# 687253_017_3_1.net
KiCad netlist of a schematic drawn in Altium Designer
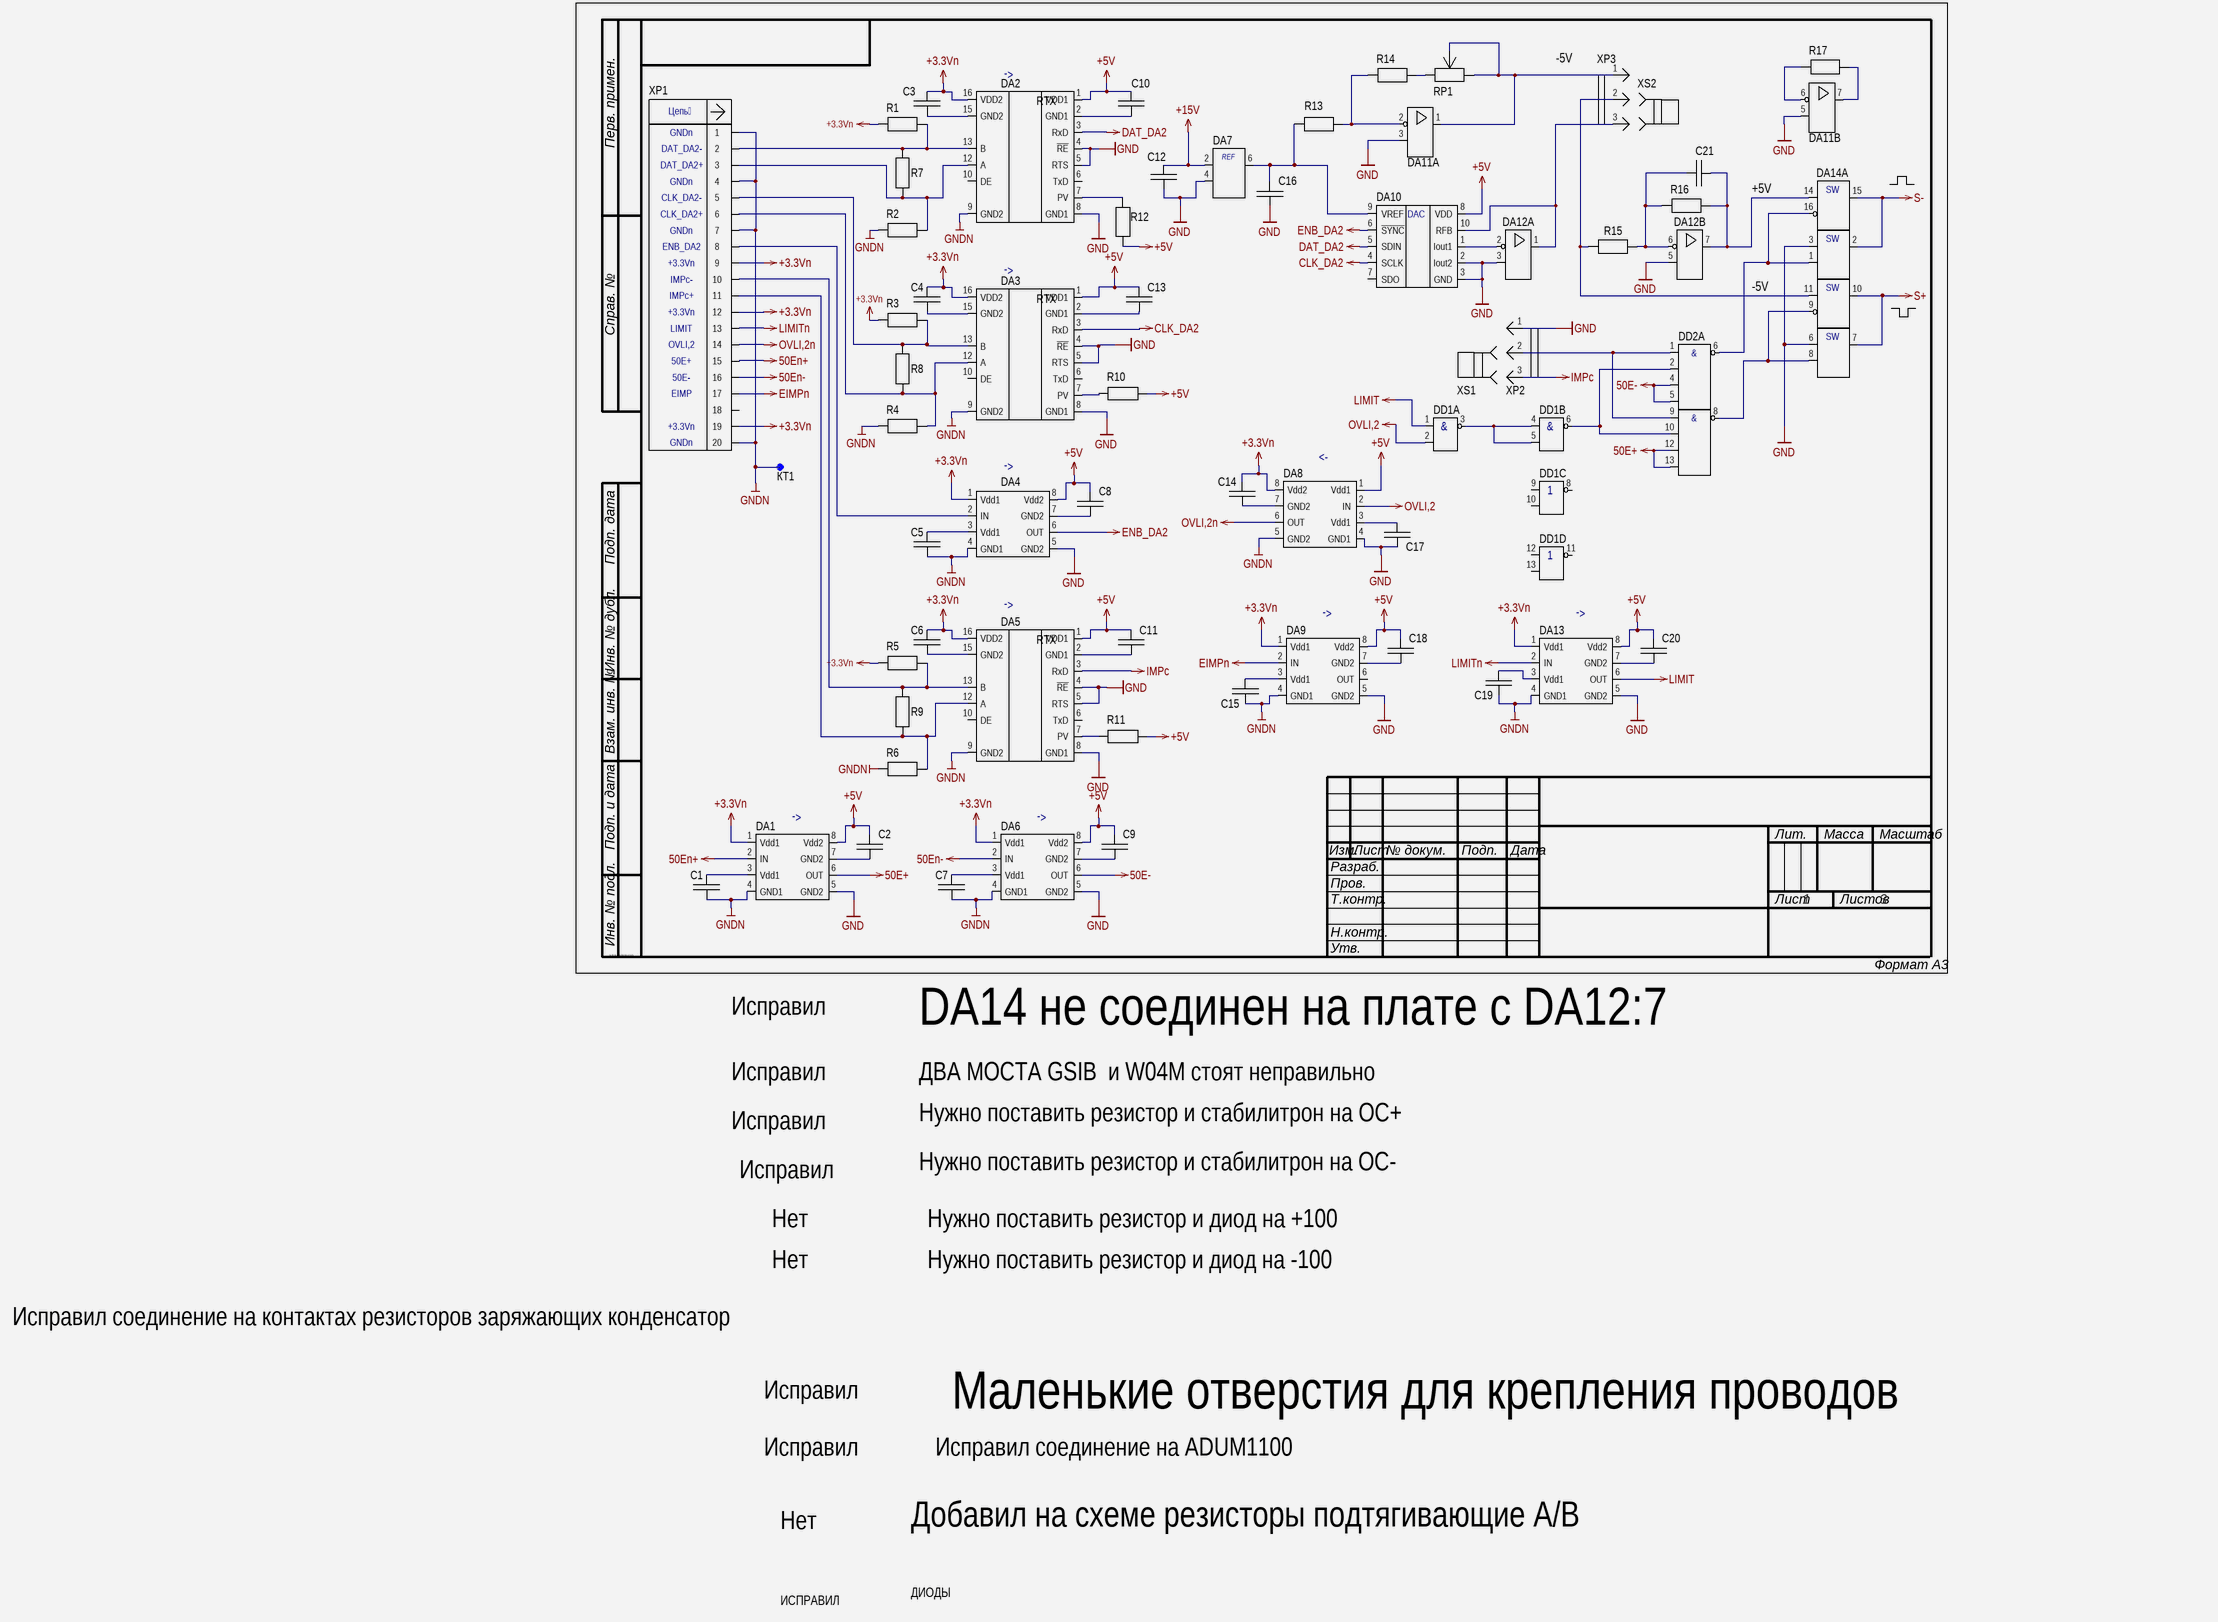
[diagram p0: УШЯИ687253.017Э3_1.SchDoc]

(export (version "E")
  (design (tool "Eeschema 10.0.6"))
  (components
    (comp (ref "C1")
      (value "0805-X7R-25 В-0,1 мкФ +-10%")
      (footprint "standard-case:CAP: 0805")
      (libsource (lib "МНИПИ_Конденсаторы") (part "0805-X7R-25 В-0,1 мкФ +-10%"))
    )
    (comp (ref "C2")
      (value "0805-X7R-25 В-0,1 мкФ +-10%")
      (footprint "standard-case:CAP: 0805")
      (libsource (lib "МНИПИ_Конденсаторы") (part "0805-X7R-25 В-0,1 мкФ +-10%"))
    )
    (comp (ref "C3")
      (value "0805-X7R-25 В-0,1 мкФ +-10%")
      (footprint "standard-case:CAP: 0805")
      (libsource (lib "МНИПИ_Конденсаторы") (part "0805-X7R-25 В-0,1 мкФ +-10%"))
    )
    (comp (ref "C4")
      (value "0805-X7R-25 В-0,1 мкФ +-10%")
      (footprint "standard-case:CAP: 0805")
      (libsource (lib "МНИПИ_Конденсаторы") (part "0805-X7R-25 В-0,1 мкФ +-10%"))
    )
    (comp (ref "C5")
      (value "0805-X7R-25 В-0,1 мкФ +-10%")
      (footprint "standard-case:CAP: 0805")
      (libsource (lib "МНИПИ_Конденсаторы") (part "0805-X7R-25 В-0,1 мкФ +-10%"))
    )
    (comp (ref "C6")
      (value "0805-X7R-25 В-0,1 мкФ +-10%")
      (footprint "standard-case:CAP: 0805")
      (libsource (lib "МНИПИ_Конденсаторы") (part "0805-X7R-25 В-0,1 мкФ +-10%"))
    )
    (comp (ref "C7")
      (value "0805-X7R-25 В-0,1 мкФ +-10%")
      (footprint "standard-case:CAP: 0805")
      (libsource (lib "МНИПИ_Конденсаторы") (part "0805-X7R-25 В-0,1 мкФ +-10%"))
    )
    (comp (ref "C8")
      (value "0805-X7R-25 В-0,1 мкФ +-10%")
      (footprint "standard-case:CAP: 0805")
      (libsource (lib "МНИПИ_Конденсаторы") (part "0805-X7R-25 В-0,1 мкФ +-10%"))
    )
    (comp (ref "C9")
      (value "0805-X7R-25 В-0,1 мкФ +-10%")
      (footprint "standard-case:CAP: 0805")
      (libsource (lib "МНИПИ_Конденсаторы") (part "0805-X7R-25 В-0,1 мкФ +-10%"))
    )
    (comp (ref "C10")
      (value "0805-X7R-25 В-0,1 мкФ +-10%")
      (footprint "standard-case:CAP: 0805")
      (libsource (lib "МНИПИ_Конденсаторы") (part "0805-X7R-25 В-0,1 мкФ +-10%"))
    )
    (comp (ref "C11")
      (value "0805-X7R-25 В-0,1 мкФ +-10%")
      (footprint "standard-case:CAP: 0805")
      (libsource (lib "МНИПИ_Конденсаторы") (part "0805-X7R-25 В-0,1 мкФ +-10%"))
    )
    (comp (ref "C12")
      (value "0805-X7R-25 В-0,1 мкФ +-10%")
      (footprint "standard-case:CAP: 0805")
      (libsource (lib "МНИПИ_Конденсаторы") (part "0805-X7R-25 В-0,1 мкФ +-10%"))
    )
    (comp (ref "C13")
      (value "0805-X7R-25 В-0,1 мкФ +-10%")
      (footprint "standard-case:CAP: 0805")
      (libsource (lib "МНИПИ_Конденсаторы") (part "0805-X7R-25 В-0,1 мкФ +-10%"))
    )
    (comp (ref "C14")
      (value "0805-X7R-25 В-0,1 мкФ +-10%")
      (footprint "standard-case:CAP: 0805")
      (libsource (lib "МНИПИ_Конденсаторы") (part "0805-X7R-25 В-0,1 мкФ +-10%"))
    )
    (comp (ref "C15")
      (value "0805-X7R-25 В-0,1 мкФ +-10%")
      (footprint "standard-case:CAP: 0805")
      (libsource (lib "МНИПИ_Конденсаторы") (part "0805-X7R-25 В-0,1 мкФ +-10%"))
    )
    (comp (ref "C16")
      (value "0805-X7R-25 В-0,1 мкФ +-10%")
      (footprint "standard-case:CAP: 0805")
      (libsource (lib "МНИПИ_Конденсаторы") (part "0805-X7R-25 В-0,1 мкФ +-10%"))
    )
    (comp (ref "C17")
      (value "0805-X7R-25 В-0,1 мкФ +-10%")
      (footprint "standard-case:CAP: 0805")
      (libsource (lib "МНИПИ_Конденсаторы") (part "0805-X7R-25 В-0,1 мкФ +-10%"))
    )
    (comp (ref "C18")
      (value "0805-X7R-25 В-0,1 мкФ +-10%")
      (footprint "standard-case:CAP: 0805")
      (libsource (lib "МНИПИ_Конденсаторы") (part "0805-X7R-25 В-0,1 мкФ +-10%"))
    )
    (comp (ref "C19")
      (value "0805-X7R-25 В-0,1 мкФ +-10%")
      (footprint "standard-case:CAP: 0805")
      (libsource (lib "МНИПИ_Конденсаторы") (part "0805-X7R-25 В-0,1 мкФ +-10%"))
    )
    (comp (ref "C20")
      (value "0805-X7R-25 В-0,1 мкФ +-10%")
      (footprint "standard-case:CAP: 0805")
      (libsource (lib "МНИПИ_Конденсаторы") (part "0805-X7R-25 В-0,1 мкФ +-10%"))
    )
    (comp (ref "C21")
      (value "1206-C0G-50 В-22 пФ +-5%")
      (footprint "standard-case:CAP: 1206")
      (libsource (lib "МНИПИ_Конденсаторы") (part "1206-C0G-50 В-22 пФ +-5%"))
    )
    (comp (ref "DA1")
      (value "ADuM1100AR")
      (footprint "standard-case:8-SOIC")
      (description "iCoupler Digital Isolator")
      (libsource (lib "МНИПИ_Микросхемы") (part "ADuM1100AR"))
    )
    (comp (ref "DA2")
      (value "ADM2486BRWZ")
      (footprint "16-SOIC-W")
      (description "Isolated RS-485 Transceiver,  20 Mbps data rate, SOIC-16-W")
      (libsource (lib "МНИПИ_Микросхемы") (part "ADM2486BRWZ"))
    )
    (comp (ref "DA3")
      (value "ADM2486BRWZ")
      (footprint "16-SOIC-W")
      (description "Isolated RS-485 Transceiver,  20 Mbps data rate, SOIC-16-W")
      (libsource (lib "МНИПИ_Микросхемы") (part "ADM2486BRWZ"))
    )
    (comp (ref "DA4")
      (value "ADuM1100AR")
      (footprint "standard-case:8-SOIC")
      (description "iCoupler Digital Isolator")
      (libsource (lib "МНИПИ_Микросхемы") (part "ADuM1100AR"))
    )
    (comp (ref "DA5")
      (value "ADM2486BRWZ")
      (footprint "16-SOIC-W")
      (description "Isolated RS-485 Transceiver,  20 Mbps data rate, SOIC-16-W")
      (libsource (lib "МНИПИ_Микросхемы") (part "ADM2486BRWZ"))
    )
    (comp (ref "DA6")
      (value "ADuM1100AR")
      (footprint "standard-case:8-SOIC")
      (description "iCoupler Digital Isolator")
      (libsource (lib "МНИПИ_Микросхемы") (part "ADuM1100AR"))
    )
    (comp (ref "DA7")
      (value "ADR435BRZ")
      (footprint "standard-case:8-SOIC")
      (libsource (lib "МНИПИ_Микросхемы") (part "ADR435BRZ"))
    )
    (comp (ref "DA8")
      (value "ADuM1100AR")
      (footprint "standard-case:8-SOIC")
      (description "iCoupler Digital Isolator")
      (libsource (lib "") (part "ADuM1100AR_1"))
    )
    (comp (ref "DA9")
      (value "ADuM1100AR")
      (footprint "standard-case:8-SOIC")
      (description "iCoupler Digital Isolator")
      (libsource (lib "МНИПИ_Микросхемы") (part "ADuM1100AR"))
    )
    (comp (ref "DA10")
      (value "AD5443YRM")
      (footprint "10-MSOP")
      (description "12-Bit High Bandwidth\r\nMultiplying DACs with Serial Interface\r10-MSOP")
      (libsource (lib "МНИПИ_Микросхемы") (part "AD5443YRM"))
    )
    (comp (ref "DA11")
      (value "ADA4084-2ARZ")
      (footprint "standard-case:8-SOIC")
      (description "30 V, Low Noise, Rail-to-Rail Input/Output,\r\nLow Power Operational Amplifiers")
      (libsource (lib "МНИПИ_Микросхемы") (part "ADA4084-2ARZ"))
    )
    (comp (ref "DA12")
      (value "ADA4084-2ARZ")
      (footprint "standard-case:8-SOIC")
      (description "30 V, Low Noise, Rail-to-Rail Input/Output,\r\nLow Power Operational Amplifiers")
      (libsource (lib "МНИПИ_Микросхемы") (part "ADA4084-2ARZ"))
    )
    (comp (ref "DA13")
      (value "ADuM1100AR")
      (footprint "standard-case:8-SOIC")
      (description "iCoupler Digital Isolator")
      (libsource (lib "МНИПИ_Микросхемы") (part "ADuM1100AR"))
    )
    (comp (ref "DA14")
      (value "ADG433BR")
      (footprint "standard-case:16-SOIC")
      (description "LC2MOS Precision Quad SPST Switches")
      (libsource (lib "МНИПИ_Микросхемы") (part "ADG433BR_1"))
    )
    (comp (ref "DD1")
      (value "IN74HC00AD")
      (footprint "standard-case:14-soic")
      (description "Quad 2-Input NAND Gate High-Performance Silicon-Gate CMOS.")
      (libsource (lib "МНИПИ_Микросхемы") (part "IN74HC00AD"))
    )
    (comp (ref "DD2")
      (value "IN74HC20D")
      (footprint "standard-case:14-SOIC")
      (description "Dual 4-input  NAND Gate CMOS")
      (libsource (lib "МНИПИ_Микросхемы") (part "IN74HC20D_1"))
    )
    (comp (ref "R1")
      (value "1206-1 кОм+-5%")
      (footprint "МНИПИ_Резисторы:1206")
      (libsource (lib "МНИПИ_Резисторы") (part "1206-1 кОм+-5%"))
    )
    (comp (ref "R2")
      (value "1206-1 кОм+-5%")
      (footprint "МНИПИ_Резисторы:1206")
      (libsource (lib "МНИПИ_Резисторы") (part "1206-1 кОм+-5%"))
    )
    (comp (ref "R3")
      (value "1206-1 кОм+-5%")
      (footprint "МНИПИ_Резисторы:1206")
      (libsource (lib "МНИПИ_Резисторы") (part "1206-1 кОм+-5%"))
    )
    (comp (ref "R4")
      (value "1206-1 кОм+-5%")
      (footprint "МНИПИ_Резисторы:1206")
      (libsource (lib "МНИПИ_Резисторы") (part "1206-1 кОм+-5%"))
    )
    (comp (ref "R5")
      (value "1206-1 кОм+-5%")
      (footprint "МНИПИ_Резисторы:1206")
      (libsource (lib "МНИПИ_Резисторы") (part "1206-1 кОм+-5%"))
    )
    (comp (ref "R6")
      (value "1206-1 кОм+-5%")
      (footprint "МНИПИ_Резисторы:1206")
      (libsource (lib "МНИПИ_Резисторы") (part "1206-1 кОм+-5%"))
    )
    (comp (ref "R7")
      (value "1206-100 Ом+-5%")
      (footprint "МНИПИ_Резисторы:1206")
      (libsource (lib "МНИПИ_Резисторы") (part "1206-100 Ом+-5%"))
    )
    (comp (ref "R8")
      (value "1206-100 Ом+-5%")
      (footprint "МНИПИ_Резисторы:1206")
      (libsource (lib "МНИПИ_Резисторы") (part "1206-100 Ом+-5%"))
    )
    (comp (ref "R9")
      (value "1206-100 Ом+-5%")
      (footprint "МНИПИ_Резисторы:1206")
      (libsource (lib "МНИПИ_Резисторы") (part "1206-100 Ом+-5%"))
    )
    (comp (ref "R10")
      (value "1206-12 кОм+-5%")
      (footprint "МНИПИ_Резисторы:1206")
      (libsource (lib "МНИПИ_Резисторы") (part "1206-12 кОм+-5%"))
    )
    (comp (ref "R11")
      (value "1206-12 кОм+-5%")
      (footprint "МНИПИ_Резисторы:1206")
      (libsource (lib "МНИПИ_Резисторы") (part "1206-12 кОм+-5%"))
    )
    (comp (ref "R12")
      (value "1206-12 кОм+-5%")
      (footprint "МНИПИ_Резисторы:1206")
      (libsource (lib "МНИПИ_Резисторы") (part "1206-12 кОм+-5%"))
    )
    (comp (ref "R13")
      (value "1206-10 кОм+-0,5%")
      (footprint "МНИПИ_Резисторы:1206")
      (libsource (lib "МНИПИ_Резисторы") (part "1206-10 кОм+-0,5%"))
    )
    (comp (ref "R14")
      (value "1206-100 Ом+-0,5%")
      (footprint "МНИПИ_Резисторы:1206")
      (libsource (lib "МНИПИ_Резисторы") (part "1206-100 Ом+-0,5%"))
    )
    (comp (ref "R15")
      (value "1206-10 кОм+-0,5%")
      (footprint "МНИПИ_Резисторы:1206")
      (libsource (lib "МНИПИ_Резисторы") (part "1206-10 кОм+-0,5%"))
    )
    (comp (ref "R16")
      (value "1206-10 кОм+-0,5%")
      (footprint "МНИПИ_Резисторы:1206")
      (libsource (lib "МНИПИ_Резисторы") (part "1206-10 кОм+-0,5%"))
    )
    (comp (ref "R17")
      (value "1206-12 кОм+-1%")
      (footprint "МНИПИ_Резисторы:1206")
      (libsource (lib "МНИПИ_Резисторы") (part "1206-12 кОм+-1%"))
    )
    (comp (ref "RP1")
      (value "3362P-1-103LF")
      (footprint "BOUR-3362P")
      (description "3362 -1/4 ˝ Square Trimpot® Trimming Potentiometer")
      (libsource (lib "МНИПИ_Резисторы") (part "3362P-1-103LF"))
    )
    (comp (ref "XP1")
      (value "BH2-20")
      (footprint "DS1014-20S")
      (description "pitch 2mm, 20 pin 2x10")
      (libsource (lib "МНИПИ_Разъемы") (part "BH2-20"))
    )
    (comp (ref "XP2")
      (value "DS1021-1x3")
      (footprint "DS1021-1x3S")
      (description "PLS-3, 2.54 pitch")
      (libsource (lib "МНИПИ_Разъемы") (part "DS1021-1x3_1"))
    )
    (comp (ref "XP3")
      (value "DS1021-1x3")
      (footprint "DS1021-1x3S")
      (description "PLS-3, 2.54 pitch")
      (libsource (lib "МНИПИ_Разъемы") (part "DS1021-1x3_1"))
    )
    (comp (ref "XS1") (value "Jumper, 2.54mm") (libsource (lib "МНИПИ_Разъемы") (part "Jumper, 2.54mm")))
    (comp (ref "XS2") (value "Jumper, 2.54mm") (libsource (lib "МНИПИ_Разъемы") (part "Jumper, 2.54mm")))
    (comp (ref "КТ1")
      (value "Лепесток")
      (footprint "LEPESTOK7750224")
      (libsource (lib "МНИПИ_Разъемы") (part "Lepestok"))
    )
  )
  (nets
    (net (code "1") (name "+3.3Vn") (class "Default")
      (node (ref "C14") (pin "1") (pinfunction "1_1") (pintype "passive"))
      (node (ref "C3") (pin "2") (pinfunction "2_2") (pintype "passive"))
      (node (ref "C4") (pin "2") (pinfunction "2_2") (pintype "passive"))
      (node (ref "C6") (pin "2") (pinfunction "2_2") (pintype "passive"))
      (node (ref "DA1") (pin "1") (pinfunction "Vdd1_1") (pintype "passive"))
      (node (ref "DA13") (pin "1") (pinfunction "Vdd1_1") (pintype "passive"))
      (node (ref "DA2") (pin "16") (pinfunction "VDD2_16") (pintype "passive"))
      (node (ref "DA3") (pin "16") (pinfunction "VDD2_16") (pintype "passive"))
      (node (ref "DA4") (pin "1") (pinfunction "Vdd1_1") (pintype "passive"))
      (node (ref "DA5") (pin "16") (pinfunction "VDD2_16") (pintype "passive"))
      (node (ref "DA6") (pin "1") (pinfunction "Vdd1_1") (pintype "passive"))
      (node (ref "DA8") (pin "8") (pinfunction "Vdd2_8") (pintype "passive"))
      (node (ref "DA9") (pin "1") (pinfunction "Vdd1_1") (pintype "passive"))
      (node (ref "R1") (pin "2") (pinfunction "2_2") (pintype "passive"))
      (node (ref "R3") (pin "2") (pinfunction "2_2") (pintype "passive"))
      (node (ref "R5") (pin "2") (pinfunction "2_2") (pintype "passive"))
      (node (ref "XP1") (pin "12") (pinfunction "12_12") (pintype "passive"))
      (node (ref "XP1") (pin "19") (pinfunction "19_19") (pintype "passive"))
      (node (ref "XP1") (pin "9") (pinfunction "9_9") (pintype "passive"))
    )
    (net (code "2") (name "+5V") (class "Default")
      (node (ref "C10") (pin "2") (pinfunction "2_2") (pintype "passive"))
      (node (ref "C11") (pin "2") (pinfunction "2_2") (pintype "passive"))
      (node (ref "C13") (pin "2") (pinfunction "2_2") (pintype "passive"))
      (node (ref "C18") (pin "1") (pinfunction "1_1") (pintype "passive"))
      (node (ref "C2") (pin "1") (pinfunction "1_1") (pintype "passive"))
      (node (ref "C20") (pin "1") (pinfunction "1_1") (pintype "passive"))
      (node (ref "C8") (pin "1") (pinfunction "1_1") (pintype "passive"))
      (node (ref "C9") (pin "1") (pinfunction "1_1") (pintype "passive"))
      (node (ref "DA1") (pin "8") (pinfunction "Vdd2_8") (pintype "passive"))
      (node (ref "DA10") (pin "8") (pinfunction "VDD_8") (pintype "passive"))
      (node (ref "DA13") (pin "8") (pinfunction "Vdd2_8") (pintype "passive"))
      (node (ref "DA2") (pin "1") (pinfunction "VDD1_1") (pintype "passive"))
      (node (ref "DA3") (pin "1") (pinfunction "VDD1_1") (pintype "passive"))
      (node (ref "DA4") (pin "8") (pinfunction "Vdd2_8") (pintype "passive"))
      (node (ref "DA5") (pin "1") (pinfunction "VDD1_1") (pintype "passive"))
      (node (ref "DA6") (pin "8") (pinfunction "Vdd2_8") (pintype "passive"))
      (node (ref "DA8") (pin "1") (pinfunction "Vdd1_1") (pintype "passive"))
      (node (ref "DA9") (pin "8") (pinfunction "Vdd2_8") (pintype "passive"))
      (node (ref "R10") (pin "1") (pinfunction "1_1") (pintype "passive"))
      (node (ref "R11") (pin "1") (pinfunction "1_1") (pintype "passive"))
      (node (ref "R12") (pin "1") (pinfunction "1_1") (pintype "passive"))
    )
    (net (code "3") (name "+15V") (class "Default")
      (node (ref "C12") (pin "1") (pinfunction "1_1") (pintype "passive"))
      (node (ref "DA7") (pin "2") (pinfunction "VIN_2") (pintype "passive"))
    )
    (net (code "4") (name "50E+") (class "Default")
      (node (ref "DA1") (pin "6") (pinfunction "OUT_6") (pintype "passive"))
      (node (ref "DD2") (pin "12") (pinfunction "C2_12") (pintype "passive"))
      (node (ref "DD2") (pin "13") (pinfunction "D2_13") (pintype "passive"))
    )
    (net (code "5") (name "50E-") (class "Default")
      (node (ref "DA6") (pin "6") (pinfunction "OUT_6") (pintype "passive"))
      (node (ref "DD2") (pin "4") (pinfunction "C1_4") (pintype "passive"))
      (node (ref "DD2") (pin "5") (pinfunction "D1_5") (pintype "passive"))
    )
    (net (code "6") (name "50En+") (class "Default")
      (node (ref "DA1") (pin "2") (pinfunction "IN_2") (pintype "passive"))
      (node (ref "XP1") (pin "15") (pinfunction "15_15") (pintype "passive"))
    )
    (net (code "7") (name "50En-") (class "Default")
      (node (ref "DA6") (pin "2") (pinfunction "IN_2") (pintype "passive"))
      (node (ref "XP1") (pin "16") (pinfunction "16_16") (pintype "passive"))
    )
    (net (code "8") (name "CLK_DA2") (class "Default")
      (node (ref "DA10") (pin "4") (pinfunction "SCLK_4") (pintype "passive"))
      (node (ref "DA3") (pin "3") (pinfunction "RxD_3") (pintype "passive"))
    )
    (net (code "9") (name "DAT_DA2") (class "Default")
      (node (ref "DA10") (pin "5") (pinfunction "SDIN_5") (pintype "passive"))
      (node (ref "DA2") (pin "3") (pinfunction "RxD_3") (pintype "passive"))
    )
    (net (code "10") (name "EIMPn") (class "Default")
      (node (ref "DA9") (pin "2") (pinfunction "IN_2") (pintype "passive"))
      (node (ref "XP1") (pin "17") (pinfunction "17_17") (pintype "passive"))
    )
    (net (code "11") (name "ENB_DA2") (class "Default")
      (node (ref "DA10") (pin "6") (pinfunction "SYNC_6") (pintype "passive"))
      (node (ref "DA4") (pin "6") (pinfunction "OUT_6") (pintype "passive"))
    )
    (net (code "12") (name "GND") (class "Default")
      (node (ref "C12") (pin "2") (pinfunction "2_2") (pintype "passive"))
      (node (ref "C16") (pin "1") (pinfunction "1_1") (pintype "passive"))
      (node (ref "C17") (pin "1") (pinfunction "1_1") (pintype "passive"))
      (node (ref "DA1") (pin "5") (pinfunction "GND2_5") (pintype "passive"))
      (node (ref "DA10") (pin "2") (pinfunction "Iout2_2") (pintype "passive"))
      (node (ref "DA10") (pin "3") (pinfunction "GND_3") (pintype "passive"))
      (node (ref "DA11") (pin "3") (pinfunction "+IN_A_3") (pintype "passive"))
      (node (ref "DA11") (pin "5") (pinfunction "+IN_B_5") (pintype "passive"))
      (node (ref "DA12") (pin "3") (pinfunction "+IN_A_3") (pintype "passive"))
      (node (ref "DA12") (pin "5") (pinfunction "+IN_B_5") (pintype "passive"))
      (node (ref "DA13") (pin "5") (pinfunction "GND2_5") (pintype "passive"))
      (node (ref "DA14") (pin "3") (pinfunction "S1_3") (pintype "passive"))
      (node (ref "DA14") (pin "6") (pinfunction "S4_6") (pintype "passive"))
      (node (ref "DA2") (pin "4") (pinfunction "RE_4") (pintype "passive"))
      (node (ref "DA2") (pin "5") (pinfunction "RTS_5") (pintype "passive"))
      (node (ref "DA2") (pin "8") (pinfunction "GND1_8") (pintype "passive"))
      (node (ref "DA3") (pin "4") (pinfunction "RE_4") (pintype "passive"))
      (node (ref "DA3") (pin "5") (pinfunction "RTS_5") (pintype "passive"))
      (node (ref "DA3") (pin "8") (pinfunction "GND1_8") (pintype "passive"))
      (node (ref "DA4") (pin "5") (pinfunction "GND2_5") (pintype "passive"))
      (node (ref "DA5") (pin "4") (pinfunction "RE_4") (pintype "passive"))
      (node (ref "DA5") (pin "5") (pinfunction "RTS_5") (pintype "passive"))
      (node (ref "DA5") (pin "8") (pinfunction "GND1_8") (pintype "passive"))
      (node (ref "DA6") (pin "5") (pinfunction "GND2_5") (pintype "passive"))
      (node (ref "DA7") (pin "4") (pinfunction "GND_4") (pintype "passive"))
      (node (ref "DA8") (pin "4") (pinfunction "GND1_4") (pintype "passive"))
      (node (ref "DA9") (pin "5") (pinfunction "GND2_5") (pintype "passive"))
      (node (ref "XP2") (pin "1") (pinfunction "1_1") (pintype "passive"))
    )
    (net (code "13") (name "GNDN") (class "Default")
      (node (ref "C1") (pin "1") (pinfunction "1_1") (pintype "passive"))
      (node (ref "C15") (pin "1") (pinfunction "1_1") (pintype "passive"))
      (node (ref "C19") (pin "1") (pinfunction "1_1") (pintype "passive"))
      (node (ref "C5") (pin "1") (pinfunction "1_1") (pintype "passive"))
      (node (ref "C7") (pin "1") (pinfunction "1_1") (pintype "passive"))
      (node (ref "DA1") (pin "4") (pinfunction "GND1_4") (pintype "passive"))
      (node (ref "DA13") (pin "4") (pinfunction "GND1_4") (pintype "passive"))
      (node (ref "DA2") (pin "9") (pinfunction "GND2_9") (pintype "passive"))
      (node (ref "DA3") (pin "9") (pinfunction "GND2_9") (pintype "passive"))
      (node (ref "DA4") (pin "4") (pinfunction "GND1_4") (pintype "passive"))
      (node (ref "DA5") (pin "9") (pinfunction "GND2_9") (pintype "passive"))
      (node (ref "DA6") (pin "4") (pinfunction "GND1_4") (pintype "passive"))
      (node (ref "DA8") (pin "5") (pinfunction "GND2_5") (pintype "passive"))
      (node (ref "DA9") (pin "4") (pinfunction "GND1_4") (pintype "passive"))
      (node (ref "R2") (pin "1") (pinfunction "1_1") (pintype "passive"))
      (node (ref "R4") (pin "1") (pinfunction "1_1") (pintype "passive"))
      (node (ref "R6") (pin "1") (pinfunction "1_1") (pintype "passive"))
      (node (ref "XP1") (pin "1") (pinfunction "1_1") (pintype "passive"))
      (node (ref "XP1") (pin "20") (pinfunction "20_20") (pintype "passive"))
      (node (ref "XP1") (pin "4") (pinfunction "4_4") (pintype "passive"))
      (node (ref "XP1") (pin "7") (pinfunction "7_7") (pintype "passive"))
      (node (ref "КТ1") (pin "1") (pinfunction "1_1") (pintype "passive"))
    )
    (net (code "14") (name "IMPc") (class "Default")
      (node (ref "DA5") (pin "3") (pinfunction "RxD_3") (pintype "passive"))
      (node (ref "XP2") (pin "3") (pinfunction "3_3") (pintype "passive"))
    )
    (net (code "15") (name "LIMIT") (class "Default")
      (node (ref "DA13") (pin "6") (pinfunction "OUT_6") (pintype "passive"))
      (node (ref "DD1") (pin "1") (pinfunction "A1_1") (pintype "passive"))
    )
    (net (code "16") (name "LIMITn") (class "Default")
      (node (ref "DA13") (pin "2") (pinfunction "IN_2") (pintype "passive"))
      (node (ref "XP1") (pin "13") (pinfunction "13_13") (pintype "passive"))
    )
    (net (code "17") (name "Net-(C1-Pad2)") (class "Default")
      (node (ref "C1") (pin "2") (pinfunction "2_2") (pintype "passive"))
      (node (ref "DA1") (pin "3") (pinfunction "Vdd1_3") (pintype "passive"))
    )
    (net (code "18") (name "Net-(C2-Pad2)") (class "Default")
      (node (ref "C2") (pin "2") (pinfunction "2_2") (pintype "passive"))
      (node (ref "DA1") (pin "7") (pinfunction "GND2_7") (pintype "passive"))
    )
    (net (code "19") (name "Net-(C3-Pad1)") (class "Default")
      (node (ref "C3") (pin "1") (pinfunction "1_1") (pintype "passive"))
      (node (ref "DA2") (pin "15") (pinfunction "GND2_15") (pintype "passive"))
    )
    (net (code "20") (name "Net-(C4-Pad1)") (class "Default")
      (node (ref "C4") (pin "1") (pinfunction "1_1") (pintype "passive"))
      (node (ref "DA3") (pin "15") (pinfunction "GND2_15") (pintype "passive"))
    )
    (net (code "21") (name "Net-(C5-Pad2)") (class "Default")
      (node (ref "C5") (pin "2") (pinfunction "2_2") (pintype "passive"))
      (node (ref "DA4") (pin "3") (pinfunction "Vdd1_3") (pintype "passive"))
    )
    (net (code "22") (name "Net-(C6-Pad1)") (class "Default")
      (node (ref "C6") (pin "1") (pinfunction "1_1") (pintype "passive"))
      (node (ref "DA5") (pin "15") (pinfunction "GND2_15") (pintype "passive"))
    )
    (net (code "23") (name "Net-(C7-Pad2)") (class "Default")
      (node (ref "C7") (pin "2") (pinfunction "2_2") (pintype "passive"))
      (node (ref "DA6") (pin "3") (pinfunction "Vdd1_3") (pintype "passive"))
    )
    (net (code "24") (name "Net-(C8-Pad2)") (class "Default")
      (node (ref "C8") (pin "2") (pinfunction "2_2") (pintype "passive"))
      (node (ref "DA4") (pin "7") (pinfunction "GND2_7") (pintype "passive"))
    )
    (net (code "25") (name "Net-(C9-Pad2)") (class "Default")
      (node (ref "C9") (pin "2") (pinfunction "2_2") (pintype "passive"))
      (node (ref "DA6") (pin "7") (pinfunction "GND2_7") (pintype "passive"))
    )
    (net (code "26") (name "Net-(C10-Pad1)") (class "Default")
      (node (ref "C10") (pin "1") (pinfunction "1_1") (pintype "passive"))
      (node (ref "DA2") (pin "2") (pinfunction "GND1_2") (pintype "passive"))
    )
    (net (code "27") (name "Net-(C11-Pad1)") (class "Default")
      (node (ref "C11") (pin "1") (pinfunction "1_1") (pintype "passive"))
      (node (ref "DA5") (pin "2") (pinfunction "GND1_2") (pintype "passive"))
    )
    (net (code "28") (name "Net-(C13-Pad1)") (class "Default")
      (node (ref "C13") (pin "1") (pinfunction "1_1") (pintype "passive"))
      (node (ref "DA3") (pin "2") (pinfunction "GND1_2") (pintype "passive"))
    )
    (net (code "29") (name "Net-(C14-Pad2)") (class "Default")
      (node (ref "C14") (pin "2") (pinfunction "2_2") (pintype "passive"))
      (node (ref "DA8") (pin "7") (pinfunction "GND2_7") (pintype "passive"))
    )
    (net (code "30") (name "Net-(C15-Pad2)") (class "Default")
      (node (ref "C15") (pin "2") (pinfunction "2_2") (pintype "passive"))
      (node (ref "DA9") (pin "3") (pinfunction "Vdd1_3") (pintype "passive"))
    )
    (net (code "31") (name "Net-(C17-Pad2)") (class "Default")
      (node (ref "C17") (pin "2") (pinfunction "2_2") (pintype "passive"))
      (node (ref "DA8") (pin "3") (pinfunction "Vdd1_3") (pintype "passive"))
    )
    (net (code "32") (name "Net-(C18-Pad2)") (class "Default")
      (node (ref "C18") (pin "2") (pinfunction "2_2") (pintype "passive"))
      (node (ref "DA9") (pin "7") (pinfunction "GND2_7") (pintype "passive"))
    )
    (net (code "33") (name "Net-(C19-Pad2)") (class "Default")
      (node (ref "C19") (pin "2") (pinfunction "2_2") (pintype "passive"))
      (node (ref "DA13") (pin "3") (pinfunction "Vdd1_3") (pintype "passive"))
    )
    (net (code "34") (name "Net-(C20-Pad2)") (class "Default")
      (node (ref "C20") (pin "2") (pinfunction "2_2") (pintype "passive"))
      (node (ref "DA13") (pin "7") (pinfunction "GND2_7") (pintype "passive"))
    )
    (net (code "35") (name "Net-(DA2-A)") (class "Default")
      (node (ref "DA2") (pin "12") (pinfunction "A_12") (pintype "passive"))
      (node (ref "R2") (pin "2") (pinfunction "2_2") (pintype "passive"))
      (node (ref "R7") (pin "1") (pinfunction "1_1") (pintype "passive"))
      (node (ref "XP1") (pin "3") (pinfunction "3_3") (pintype "passive"))
    )
    (net (code "36") (name "Net-(DA2-B)") (class "Default")
      (node (ref "DA2") (pin "13") (pinfunction "B_13") (pintype "passive"))
      (node (ref "R1") (pin "1") (pinfunction "1_1") (pintype "passive"))
      (node (ref "R7") (pin "2") (pinfunction "1_2") (pintype "passive"))
      (node (ref "XP1") (pin "2") (pinfunction "2_2") (pintype "passive"))
    )
    (net (code "37") (name "Net-(DA2-PV)") (class "Default")
      (node (ref "DA2") (pin "7") (pinfunction "PV_7") (pintype "passive"))
      (node (ref "R12") (pin "2") (pinfunction "2_2") (pintype "passive"))
    )
    (net (code "38") (name "Net-(DA3-A)") (class "Default")
      (node (ref "DA3") (pin "12") (pinfunction "A_12") (pintype "passive"))
      (node (ref "R4") (pin "2") (pinfunction "2_2") (pintype "passive"))
      (node (ref "R8") (pin "1") (pinfunction "1_1") (pintype "passive"))
      (node (ref "XP1") (pin "6") (pinfunction "6_6") (pintype "passive"))
    )
    (net (code "39") (name "Net-(DA3-B)") (class "Default")
      (node (ref "DA3") (pin "13") (pinfunction "B_13") (pintype "passive"))
      (node (ref "R3") (pin "1") (pinfunction "1_1") (pintype "passive"))
      (node (ref "R8") (pin "2") (pinfunction "1_2") (pintype "passive"))
      (node (ref "XP1") (pin "5") (pinfunction "5_5") (pintype "passive"))
    )
    (net (code "40") (name "Net-(DA3-PV)") (class "Default")
      (node (ref "DA3") (pin "7") (pinfunction "PV_7") (pintype "passive"))
      (node (ref "R10") (pin "2") (pinfunction "2_2") (pintype "passive"))
    )
    (net (code "41") (name "Net-(DA4-IN)") (class "Default")
      (node (ref "DA4") (pin "2") (pinfunction "IN_2") (pintype "passive"))
      (node (ref "XP1") (pin "8") (pinfunction "8_8") (pintype "passive"))
    )
    (net (code "42") (name "Net-(DA5-A)") (class "Default")
      (node (ref "DA5") (pin "12") (pinfunction "A_12") (pintype "passive"))
      (node (ref "R6") (pin "2") (pinfunction "2_2") (pintype "passive"))
      (node (ref "R9") (pin "1") (pinfunction "1_1") (pintype "passive"))
      (node (ref "XP1") (pin "11") (pinfunction "11_11") (pintype "passive"))
    )
    (net (code "43") (name "Net-(DA5-B)") (class "Default")
      (node (ref "DA5") (pin "13") (pinfunction "B_13") (pintype "passive"))
      (node (ref "R5") (pin "1") (pinfunction "1_1") (pintype "passive"))
      (node (ref "R9") (pin "2") (pinfunction "1_2") (pintype "passive"))
      (node (ref "XP1") (pin "10") (pinfunction "10_10") (pintype "passive"))
    )
    (net (code "44") (name "Net-(DA5-PV)") (class "Default")
      (node (ref "DA5") (pin "7") (pinfunction "PV_7") (pintype "passive"))
      (node (ref "R11") (pin "2") (pinfunction "2_2") (pintype "passive"))
    )
    (net (code "45") (name "Net-(DA10-Iout1)") (class "Default")
      (node (ref "DA10") (pin "1") (pinfunction "Iout1_1") (pintype "passive"))
      (node (ref "DA12") (pin "2") (pinfunction "-IN_A_2") (pintype "passive"))
    )
    (net (code "46") (name "Net-(DA10-RFB)") (class "Default")
      (node (ref "DA10") (pin "10") (pinfunction "RFB_10") (pintype "passive"))
      (node (ref "DA12") (pin "1") (pinfunction "OUT_A_1") (pintype "passive"))
      (node (ref "XP3") (pin "3") (pinfunction "3_3") (pintype "passive"))
    )
    (net (code "47") (name "Net-(DA10-VREF)") (class "Default")
      (node (ref "C16") (pin "2") (pinfunction "2_2") (pintype "passive"))
      (node (ref "DA10") (pin "9") (pinfunction "VREF_9") (pintype "passive"))
      (node (ref "DA7") (pin "6") (pinfunction "VOUT_6") (pintype "passive"))
      (node (ref "R13") (pin "1") (pinfunction "1_1") (pintype "passive"))
    )
    (net (code "48") (name "Net-(DA11A--IN_A)") (class "Default")
      (node (ref "DA11") (pin "2") (pinfunction "-IN_A_2") (pintype "passive"))
      (node (ref "R13") (pin "2") (pinfunction "2_2") (pintype "passive"))
      (node (ref "R14") (pin "1") (pinfunction "1_1") (pintype "passive"))
    )
    (net (code "49") (name "Net-(DA11A-OUT_A)") (class "Default")
      (node (ref "DA11") (pin "1") (pinfunction "OUT_A_1") (pintype "passive"))
      (node (ref "RP1") (pin "1") (pintype "passive"))
      (node (ref "RP1") (pin "2") (pinfunction "WIPER_2") (pintype "passive"))
      (node (ref "XP3") (pin "1") (pinfunction "1_1") (pintype "passive"))
    )
    (net (code "50") (name "Net-(DA11B--IN_B)") (class "Default")
      (node (ref "DA11") (pin "6") (pinfunction "-IN_B_6") (pintype "passive"))
      (node (ref "R17") (pin "1") (pinfunction "1_1") (pintype "passive"))
    )
    (net (code "51") (name "Net-(DA11B-OUT_B)") (class "Default")
      (node (ref "DA11") (pin "7") (pinfunction "OUT_B_7") (pintype "passive"))
      (node (ref "R17") (pin "2") (pinfunction "2_2") (pintype "passive"))
    )
    (net (code "52") (name "Net-(DA12B--IN_B)") (class "Default")
      (node (ref "C21") (pin "1") (pinfunction "1_1") (pintype "passive"))
      (node (ref "DA12") (pin "6") (pinfunction "-IN_B_6") (pintype "passive"))
      (node (ref "R15") (pin "2") (pinfunction "2_2") (pintype "passive"))
      (node (ref "R16") (pin "1") (pinfunction "1_1") (pintype "passive"))
    )
    (net (code "53") (name "Net-(DA12B-OUT_B)") (class "Default")
      (node (ref "C21") (pin "2") (pinfunction "2_2") (pintype "passive"))
      (node (ref "DA12") (pin "7") (pinfunction "OUT_B_7") (pintype "passive"))
      (node (ref "DA14") (pin "14") (pinfunction "S2_14") (pintype "passive"))
      (node (ref "R16") (pin "2") (pinfunction "2_2") (pintype "passive"))
    )
    (net (code "54") (name "Net-(DA14A-IN1)") (class "Default")
      (node (ref "DA14") (pin "1") (pinfunction "IN1_1") (pintype "passive"))
      (node (ref "DA14") (pin "16") (pinfunction "IN2_16") (pintype "passive"))
      (node (ref "DD2") (pin "6") (pinfunction "Y1_6") (pintype "passive"))
    )
    (net (code "55") (name "Net-(DA14A-IN3)") (class "Default")
      (node (ref "DA14") (pin "8") (pinfunction "IN4_8") (pintype "passive"))
      (node (ref "DA14") (pin "9") (pinfunction "IN3_9") (pintype "passive"))
      (node (ref "DD2") (pin "8") (pinfunction "Y2_8") (pintype "passive"))
    )
    (net (code "56") (name "Net-(DA14A-S3)") (class "Default")
      (node (ref "DA14") (pin "11") (pinfunction "S3_11") (pintype "passive"))
      (node (ref "R15") (pin "1") (pinfunction "1_1") (pintype "passive"))
      (node (ref "XP3") (pin "2") (pinfunction "2_2") (pintype "passive"))
    )
    (net (code "57") (name "Net-(DD1A-Y1)") (class "Default")
      (node (ref "DD1") (pin "3") (pinfunction "Y1_3") (pintype "passive"))
      (node (ref "DD1") (pin "4") (pinfunction "A2_4") (pintype "passive"))
      (node (ref "DD1") (pin "5") (pinfunction "B2_5") (pintype "passive"))
    )
    (net (code "58") (name "Net-(DD1B-Y2)") (class "Default")
      (node (ref "DD1") (pin "6") (pinfunction "Y2_6") (pintype "passive"))
      (node (ref "DD2") (pin "10") (pinfunction "B2_10") (pintype "passive"))
      (node (ref "DD2") (pin "2") (pinfunction "B1_2") (pintype "passive"))
    )
    (net (code "59") (name "Net-(DD2A-A1)") (class "Default")
      (node (ref "DD2") (pin "1") (pinfunction "A1_1") (pintype "passive"))
      (node (ref "DD2") (pin "9") (pinfunction "A2_9") (pintype "passive"))
      (node (ref "XP2") (pin "2") (pinfunction "2_2") (pintype "passive"))
    )
    (net (code "60") (name "Net-(R14-1-Pad2)") (class "Default")
      (node (ref "R14") (pin "2") (pinfunction "1_2") (pintype "passive"))
      (node (ref "RP1") (pin "3") (pintype "passive"))
    )
    (net (code "61") (name "OVLI,2") (class "Default")
      (node (ref "DA8") (pin "2") (pinfunction "IN_2") (pintype "passive"))
      (node (ref "DD1") (pin "2") (pinfunction "B1_2") (pintype "passive"))
    )
    (net (code "62") (name "OVLI,2n") (class "Default")
      (node (ref "DA8") (pin "6") (pinfunction "OUT_6") (pintype "passive"))
      (node (ref "XP1") (pin "14") (pinfunction "14_14") (pintype "passive"))
    )
    (net (code "63") (name "S+") (class "Default")
      (node (ref "DA14") (pin "10") (pinfunction "D3_10") (pintype "passive"))
      (node (ref "DA14") (pin "7") (pinfunction "D4_7") (pintype "passive"))
    )
    (net (code "64") (name "S-") (class "Default")
      (node (ref "DA14") (pin "15") (pinfunction "D2_15") (pintype "passive"))
      (node (ref "DA14") (pin "2") (pinfunction "D1_2") (pintype "passive"))
    )
    (net (code "65") (name "unconnected-(DA2-DE-Pad10)") (class "Default")
      (node (ref "DA2") (pin "10") (pinfunction "DE_10") (pintype "passive"))
    )
    (net (code "66") (name "unconnected-(DA2-TxD-Pad6)") (class "Default")
      (node (ref "DA2") (pin "6") (pinfunction "TxD_6") (pintype "passive"))
    )
    (net (code "67") (name "unconnected-(DA3-DE-Pad10)") (class "Default")
      (node (ref "DA3") (pin "10") (pinfunction "DE_10") (pintype "passive"))
    )
    (net (code "68") (name "unconnected-(DA3-TxD-Pad6)") (class "Default")
      (node (ref "DA3") (pin "6") (pinfunction "TxD_6") (pintype "passive"))
    )
    (net (code "69") (name "unconnected-(DA5-DE-Pad10)") (class "Default")
      (node (ref "DA5") (pin "10") (pinfunction "DE_10") (pintype "passive"))
    )
    (net (code "70") (name "unconnected-(DA5-TxD-Pad6)") (class "Default")
      (node (ref "DA5") (pin "6") (pinfunction "TxD_6") (pintype "passive"))
    )
    (net (code "71") (name "unconnected-(DA9-OUT-Pad6)") (class "Default")
      (node (ref "DA9") (pin "6") (pinfunction "OUT_6") (pintype "passive"))
    )
    (net (code "72") (name "unconnected-(DA10-SDO-Pad7)") (class "Default")
      (node (ref "DA10") (pin "7") (pinfunction "SDO_7") (pintype "passive"))
    )
    (net (code "73") (name "unconnected-(DD1C-A3-Pad9)") (class "Default")
      (node (ref "DD1") (pin "9") (pinfunction "A3_9") (pintype "passive"))
    )
    (net (code "74") (name "unconnected-(DD1C-B3-Pad10)") (class "Default")
      (node (ref "DD1") (pin "10") (pinfunction "B3_10") (pintype "passive"))
    )
    (net (code "75") (name "unconnected-(DD1C-Y3-Pad8)") (class "Default")
      (node (ref "DD1") (pin "8") (pinfunction "Y3_8") (pintype "passive"))
    )
    (net (code "76") (name "unconnected-(DD1D-A4-Pad12)") (class "Default")
      (node (ref "DD1") (pin "12") (pinfunction "A4_12") (pintype "passive"))
    )
    (net (code "77") (name "unconnected-(DD1D-B4-Pad13)") (class "Default")
      (node (ref "DD1") (pin "13") (pinfunction "B4_13") (pintype "passive"))
    )
    (net (code "78") (name "unconnected-(DD1D-Y4-Pad11)") (class "Default")
      (node (ref "DD1") (pin "11") (pinfunction "Y4_11") (pintype "passive"))
    )
    (net (code "79") (name "unconnected-(XP1-Pad18)") (class "Default")
      (node (ref "XP1") (pin "18") (pinfunction "18_18") (pintype "passive"))
    )
  )
)
